# MCU.net
KiCad netlist of a schematic drawn in Altium Designer
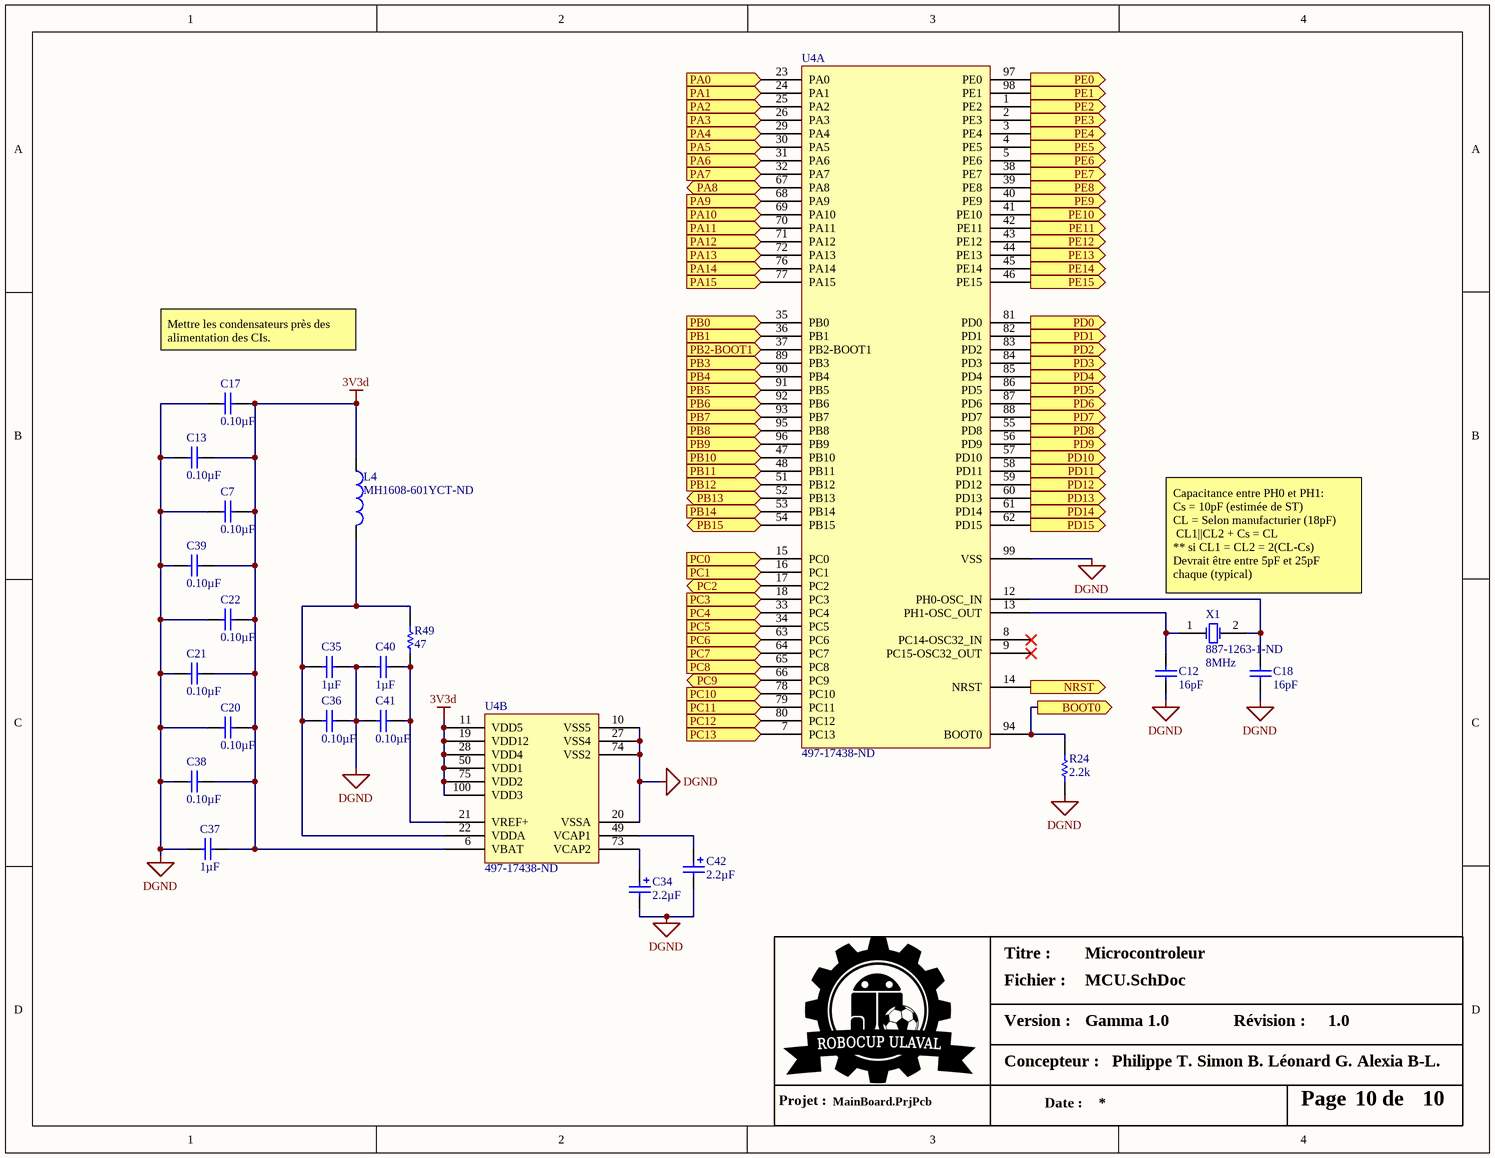
[diagram p0: MCU.SchDoc]

(export (version "E")
  (design (tool "Eeschema 10.0.6"))
  (components
    (comp (ref "C7")
      (value "CL10B104KB8SFNC")
      (footprint "0603")
      (description "CAP CER 0.1UF 50V X7R 0603")
      (fields
        (field (name "MANUFACTURER") "Samsung Electro-Mechanics America, Inc.")
        (field (name "TOLERANCE") "±10%")
        (field (name "CAPACITANCE") "0.10µF")
      )
      (libsource (lib "ResCap") (part "CL10B104KB8SFNC"))
    )
    (comp (ref "C12")
      (value "CL10C160JB8NNNC")
      (footprint "0603")
      (description "CAP CER 16PF 50V NP0 0603")
      (fields
        (field (name "MANUFACTURER") "Samsung Electro-Mechanics America, Inc.")
        (field (name "TOLERANCE") "±5%")
        (field (name "CAPACITANCE") "16pF")
      )
      (libsource (lib "ResCap") (part "CL10C160JB8NNNC"))
    )
    (comp (ref "C13")
      (value "CL10B104KB8SFNC")
      (footprint "0603")
      (description "CAP CER 0.1UF 50V X7R 0603")
      (fields
        (field (name "MANUFACTURER") "Samsung Electro-Mechanics America, Inc.")
        (field (name "TOLERANCE") "±10%")
        (field (name "CAPACITANCE") "0.10µF")
      )
      (libsource (lib "ResCap") (part "CL10B104KB8SFNC"))
    )
    (comp (ref "C17")
      (value "CL10B104KB8SFNC")
      (footprint "0603")
      (description "CAP CER 0.1UF 50V X7R 0603")
      (fields
        (field (name "MANUFACTURER") "Samsung Electro-Mechanics America, Inc.")
        (field (name "TOLERANCE") "±10%")
        (field (name "CAPACITANCE") "0.10µF")
      )
      (libsource (lib "ResCap") (part "CL10B104KB8SFNC"))
    )
    (comp (ref "C18")
      (value "CL10C160JB8NNNC")
      (footprint "0603")
      (description "CAP CER 16PF 50V NP0 0603")
      (fields
        (field (name "MANUFACTURER") "Samsung Electro-Mechanics America, Inc.")
        (field (name "TOLERANCE") "±5%")
        (field (name "CAPACITANCE") "16pF")
      )
      (libsource (lib "ResCap") (part "CL10C160JB8NNNC"))
    )
    (comp (ref "C20")
      (value "CL10B104KB8SFNC")
      (footprint "0603")
      (description "CAP CER 0.1UF 50V X7R 0603")
      (fields
        (field (name "MANUFACTURER") "Samsung Electro-Mechanics America, Inc.")
        (field (name "TOLERANCE") "±10%")
        (field (name "CAPACITANCE") "0.10µF")
      )
      (libsource (lib "ResCap") (part "CL10B104KB8SFNC"))
    )
    (comp (ref "C21")
      (value "CL10B104KB8SFNC")
      (footprint "0603")
      (description "CAP CER 0.1UF 50V X7R 0603")
      (fields
        (field (name "MANUFACTURER") "Samsung Electro-Mechanics America, Inc.")
        (field (name "TOLERANCE") "±10%")
        (field (name "CAPACITANCE") "0.10µF")
      )
      (libsource (lib "ResCap") (part "CL10B104KB8SFNC"))
    )
    (comp (ref "C22")
      (value "CL10B104KB8SFNC")
      (footprint "0603")
      (description "CAP CER 0.1UF 50V X7R 0603")
      (fields
        (field (name "MANUFACTURER") "Samsung Electro-Mechanics America, Inc.")
        (field (name "TOLERANCE") "±10%")
        (field (name "CAPACITANCE") "0.10µF")
      )
      (libsource (lib "ResCap") (part "CL10B104KB8SFNC"))
    )
    (comp (ref "C34")
      (value "865060640002")
      (footprint "CAP 4.3x4.3mm")
      (description "CAP 2.2 UF 20% 50 V")
      (fields
        (field (name "MANUFACTURER") "Wurth Electronics Inc")
        (field (name "TOLERANCE") "±20%")
        (field (name "CAPACITANCE") "2.2µF")
      )
      (libsource (lib "ResCap") (part "865060640002"))
    )
    (comp (ref "C35")
      (value "CL21B105KBFNFNE")
      (footprint "0805")
      (description "CAP CER 1UF 50V X7R 0805")
      (fields
        (field (name "MANUFACTURER") "Samsung Electro-Mechanics America, Inc.")
        (field (name "TOLERANCE") "±10%")
        (field (name "CAPACITANCE") "1µF")
      )
      (libsource (lib "ResCap") (part "CL21B105KBFNFNE"))
    )
    (comp (ref "C36")
      (value "CL10B104KB8SFNC")
      (footprint "0603")
      (description "CAP CER 0.1UF 50V X7R 0603")
      (fields
        (field (name "MANUFACTURER") "Samsung Electro-Mechanics America, Inc.")
        (field (name "TOLERANCE") "±10%")
        (field (name "CAPACITANCE") "0.10µF")
      )
      (libsource (lib "ResCap") (part "CL10B104KB8SFNC"))
    )
    (comp (ref "C37")
      (value "CL21B105KBFNFNE")
      (footprint "0805")
      (description "CAP CER 1UF 50V X7R 0805")
      (fields
        (field (name "MANUFACTURER") "Samsung Electro-Mechanics America, Inc.")
        (field (name "TOLERANCE") "±10%")
        (field (name "CAPACITANCE") "1µF")
      )
      (libsource (lib "ResCap") (part "CL21B105KBFNFNE"))
    )
    (comp (ref "C38")
      (value "CL10B104KB8SFNC")
      (footprint "0603")
      (description "CAP CER 0.1UF 50V X7R 0603")
      (fields
        (field (name "MANUFACTURER") "Samsung Electro-Mechanics America, Inc.")
        (field (name "TOLERANCE") "±10%")
        (field (name "CAPACITANCE") "0.10µF")
      )
      (libsource (lib "ResCap") (part "CL10B104KB8SFNC"))
    )
    (comp (ref "C39")
      (value "CL10B104KB8SFNC")
      (footprint "0603")
      (description "CAP CER 0.1UF 50V X7R 0603")
      (fields
        (field (name "MANUFACTURER") "Samsung Electro-Mechanics America, Inc.")
        (field (name "TOLERANCE") "±10%")
        (field (name "CAPACITANCE") "0.10µF")
      )
      (libsource (lib "ResCap") (part "CL10B104KB8SFNC"))
    )
    (comp (ref "C40")
      (value "CL21B105KBFNFNE")
      (footprint "0805")
      (description "CAP CER 1UF 50V X7R 0805")
      (fields
        (field (name "MANUFACTURER") "Samsung Electro-Mechanics America, Inc.")
        (field (name "TOLERANCE") "±10%")
        (field (name "CAPACITANCE") "1µF")
      )
      (libsource (lib "ResCap") (part "CL21B105KBFNFNE"))
    )
    (comp (ref "C41")
      (value "CL10B104KB8SFNC")
      (footprint "0603")
      (description "CAP CER 0.1UF 50V X7R 0603")
      (fields
        (field (name "MANUFACTURER") "Samsung Electro-Mechanics America, Inc.")
        (field (name "TOLERANCE") "±10%")
        (field (name "CAPACITANCE") "0.10µF")
      )
      (libsource (lib "ResCap") (part "CL10B104KB8SFNC"))
    )
    (comp (ref "C42")
      (value "865060640002")
      (footprint "CAP 4.3x4.3mm")
      (description "CAP 2.2 UF 20% 50 V")
      (fields
        (field (name "MANUFACTURER") "Wurth Electronics Inc")
        (field (name "TOLERANCE") "±20%")
        (field (name "CAPACITANCE") "2.2µF")
      )
      (libsource (lib "ResCap") (part "865060640002"))
    )
    (comp (ref "L4")
      (value "MH1608-601Y")
      (footprint "0603")
      (description "FERRITE BEAD 600 OHM 0603 1LN")
      (fields
        (field (name "MANUFACTURER") "Bourns Inc.")
        (field (name "SUPPLIER PART NUMBER 1") "MH1608-601YCT-ND")
      )
      (libsource (lib "MainBoard") (part "MH1608-601Y"))
    )
    (comp (ref "R24")
      (value "RC0603FR-072K2L")
      (footprint "0603")
      (description "RES SMD 2.2K OHM 1% 1/10W 0603")
      (fields
        (field (name "MANUFACTURER") "Yageo")
        (field (name "TOLERANCE") "±1%")
        (field (name "RESISTANCE (OHMS)") "2.2k")
      )
      (libsource (lib "ResCap") (part "RC0603FR-072K2L"))
    )
    (comp (ref "R49")
      (value "RC0603JR-0747RL")
      (footprint "0603")
      (description "RES SMD 47 OHM 5% 1/10W 0603")
      (fields
        (field (name "MANUFACTURER") "Yageo")
        (field (name "TOLERANCE") "±5%")
        (field (name "RESISTANCE (OHMS)") "47")
      )
      (libsource (lib "ResCap") (part "RC0603JR-0747RL"))
    )
    (comp (ref "U4")
      (value "STM32F407VGT6")
      (footprint "TSQFP50P1600X1600X160-100N")
      (description "IC MCU 32BIT 1MB FLASH 100LQFP")
      (fields
        (field (name "MANUFACTURER") "STMicroelectronics")
        (field (name "SUPPLIER PART NUMBER 1") "497-17438-ND")
      )
      (libsource (lib "MainBoard") (part "STM32F407VGT6"))
    )
    (comp (ref "X1")
      (value "9C-8.000MEEJ-T")
      (footprint "HC49/US")
      (description "CRYSTAL 8.0000MHZ 18PF SMD")
      (fields
        (field (name "MANUFACTURER") "TXC CORPORATION")
        (field (name "SUPPLIER PART NUMBER 1") "887-1263-1-ND")
        (field (name "FREQUENCY") "8MHz")
      )
      (libsource (lib "MainBoard") (part "9C-8.000MEEJ-T"))
    )
  )
  (nets
    (net (code "1") (name "/BOOT0") (class "Default")
      (node (ref "R24") (pin "2") (pinfunction "2_2") (pintype "passive"))
      (node (ref "U4") (pin "94") (pinfunction "BOOT0_94") (pintype "passive"))
    )
    (net (code "2") (name "/NRST") (class "Default")
      (node (ref "U4") (pin "14") (pinfunction "NRST_14") (pintype "passive"))
    )
    (net (code "3") (name "/PA0") (class "Default")
      (node (ref "U4") (pin "23") (pinfunction "PA0_23") (pintype "passive"))
    )
    (net (code "4") (name "/PA1") (class "Default")
      (node (ref "U4") (pin "24") (pinfunction "PA1_24") (pintype "passive"))
    )
    (net (code "5") (name "/PA2") (class "Default")
      (node (ref "U4") (pin "25") (pinfunction "PA2_25") (pintype "passive"))
    )
    (net (code "6") (name "/PA3") (class "Default")
      (node (ref "U4") (pin "26") (pinfunction "PA3_26") (pintype "passive"))
    )
    (net (code "7") (name "/PA4") (class "Default")
      (node (ref "U4") (pin "29") (pinfunction "PA4_29") (pintype "passive"))
    )
    (net (code "8") (name "/PA5") (class "Default")
      (node (ref "U4") (pin "30") (pinfunction "PA5_30") (pintype "passive"))
    )
    (net (code "9") (name "/PA6") (class "Default")
      (node (ref "U4") (pin "31") (pinfunction "PA6_31") (pintype "passive"))
    )
    (net (code "10") (name "/PA7") (class "Default")
      (node (ref "U4") (pin "32") (pinfunction "PA7_32") (pintype "passive"))
    )
    (net (code "11") (name "/PA8") (class "Default")
      (node (ref "U4") (pin "67") (pinfunction "PA8_67") (pintype "passive"))
    )
    (net (code "12") (name "/PA9") (class "Default")
      (node (ref "U4") (pin "68") (pinfunction "PA9_68") (pintype "passive"))
    )
    (net (code "13") (name "/PA10") (class "Default")
      (node (ref "U4") (pin "69") (pinfunction "PA10_69") (pintype "passive"))
    )
    (net (code "14") (name "/PA11") (class "Default")
      (node (ref "U4") (pin "70") (pinfunction "PA11_70") (pintype "passive"))
    )
    (net (code "15") (name "/PA12") (class "Default")
      (node (ref "U4") (pin "71") (pinfunction "PA12_71") (pintype "passive"))
    )
    (net (code "16") (name "/PA13") (class "Default")
      (node (ref "U4") (pin "72") (pinfunction "PA13_72") (pintype "passive"))
    )
    (net (code "17") (name "/PA14") (class "Default")
      (node (ref "U4") (pin "76") (pinfunction "PA14_76") (pintype "passive"))
    )
    (net (code "18") (name "/PA15") (class "Default")
      (node (ref "U4") (pin "77") (pinfunction "PA15_77") (pintype "passive"))
    )
    (net (code "19") (name "/PB0") (class "Default")
      (node (ref "U4") (pin "35") (pinfunction "PB0_35") (pintype "passive"))
    )
    (net (code "20") (name "/PB1") (class "Default")
      (node (ref "U4") (pin "36") (pinfunction "PB1_36") (pintype "passive"))
    )
    (net (code "21") (name "/PB2-BOOT1") (class "Default")
      (node (ref "U4") (pin "37") (pinfunction "PB2-BOOT1_37") (pintype "passive"))
    )
    (net (code "22") (name "/PB3") (class "Default")
      (node (ref "U4") (pin "89") (pinfunction "PB3_89") (pintype "passive"))
    )
    (net (code "23") (name "/PB4") (class "Default")
      (node (ref "U4") (pin "90") (pinfunction "PB4_90") (pintype "passive"))
    )
    (net (code "24") (name "/PB5") (class "Default")
      (node (ref "U4") (pin "91") (pinfunction "PB5_91") (pintype "passive"))
    )
    (net (code "25") (name "/PB6") (class "Default")
      (node (ref "U4") (pin "92") (pinfunction "PB6_92") (pintype "passive"))
    )
    (net (code "26") (name "/PB7") (class "Default")
      (node (ref "U4") (pin "93") (pinfunction "PB7_93") (pintype "passive"))
    )
    (net (code "27") (name "/PB8") (class "Default")
      (node (ref "U4") (pin "95") (pinfunction "PB8_95") (pintype "passive"))
    )
    (net (code "28") (name "/PB9") (class "Default")
      (node (ref "U4") (pin "96") (pinfunction "PB9_96") (pintype "passive"))
    )
    (net (code "29") (name "/PB10") (class "Default")
      (node (ref "U4") (pin "47") (pinfunction "PB10_47") (pintype "passive"))
    )
    (net (code "30") (name "/PB11") (class "Default")
      (node (ref "U4") (pin "48") (pinfunction "PB11_48") (pintype "passive"))
    )
    (net (code "31") (name "/PB12") (class "Default")
      (node (ref "U4") (pin "51") (pinfunction "PB12_51") (pintype "passive"))
    )
    (net (code "32") (name "/PB13") (class "Default")
      (node (ref "U4") (pin "52") (pinfunction "PB13_52") (pintype "passive"))
    )
    (net (code "33") (name "/PB14") (class "Default")
      (node (ref "U4") (pin "53") (pinfunction "PB14_53") (pintype "passive"))
    )
    (net (code "34") (name "/PB15") (class "Default")
      (node (ref "U4") (pin "54") (pinfunction "PB15_54") (pintype "passive"))
    )
    (net (code "35") (name "/PC0") (class "Default")
      (node (ref "U4") (pin "15") (pinfunction "PC0_15") (pintype "passive"))
    )
    (net (code "36") (name "/PC1") (class "Default")
      (node (ref "U4") (pin "16") (pinfunction "PC1_16") (pintype "passive"))
    )
    (net (code "37") (name "/PC2") (class "Default")
      (node (ref "U4") (pin "17") (pinfunction "PC2_17") (pintype "passive"))
    )
    (net (code "38") (name "/PC3") (class "Default")
      (node (ref "U4") (pin "18") (pinfunction "PC3_18") (pintype "passive"))
    )
    (net (code "39") (name "/PC4") (class "Default")
      (node (ref "U4") (pin "33") (pinfunction "PC4_33") (pintype "passive"))
    )
    (net (code "40") (name "/PC5") (class "Default")
      (node (ref "U4") (pin "34") (pinfunction "PC5_34") (pintype "passive"))
    )
    (net (code "41") (name "/PC6") (class "Default")
      (node (ref "U4") (pin "63") (pinfunction "PC6_63") (pintype "passive"))
    )
    (net (code "42") (name "/PC7") (class "Default")
      (node (ref "U4") (pin "64") (pinfunction "PC7_64") (pintype "passive"))
    )
    (net (code "43") (name "/PC8") (class "Default")
      (node (ref "U4") (pin "65") (pinfunction "PC8_65") (pintype "passive"))
    )
    (net (code "44") (name "/PC9") (class "Default")
      (node (ref "U4") (pin "66") (pinfunction "PC9_66") (pintype "passive"))
    )
    (net (code "45") (name "/PC10") (class "Default")
      (node (ref "U4") (pin "78") (pinfunction "PC10_78") (pintype "passive"))
    )
    (net (code "46") (name "/PC11") (class "Default")
      (node (ref "U4") (pin "79") (pinfunction "PC11_79") (pintype "passive"))
    )
    (net (code "47") (name "/PC12") (class "Default")
      (node (ref "U4") (pin "80") (pinfunction "PC12_80") (pintype "passive"))
    )
    (net (code "48") (name "/PC13") (class "Default")
      (node (ref "U4") (pin "7") (pinfunction "PC13_7") (pintype "passive"))
    )
    (net (code "49") (name "/PD0") (class "Default")
      (node (ref "U4") (pin "81") (pinfunction "PD0_81") (pintype "passive"))
    )
    (net (code "50") (name "/PD1") (class "Default")
      (node (ref "U4") (pin "82") (pinfunction "PD1_82") (pintype "passive"))
    )
    (net (code "51") (name "/PD2") (class "Default")
      (node (ref "U4") (pin "83") (pinfunction "PD2_83") (pintype "passive"))
    )
    (net (code "52") (name "/PD3") (class "Default")
      (node (ref "U4") (pin "84") (pinfunction "PD3_84") (pintype "passive"))
    )
    (net (code "53") (name "/PD4") (class "Default")
      (node (ref "U4") (pin "85") (pinfunction "PD4_85") (pintype "passive"))
    )
    (net (code "54") (name "/PD5") (class "Default")
      (node (ref "U4") (pin "86") (pinfunction "PD5_86") (pintype "passive"))
    )
    (net (code "55") (name "/PD6") (class "Default")
      (node (ref "U4") (pin "87") (pinfunction "PD6_87") (pintype "passive"))
    )
    (net (code "56") (name "/PD7") (class "Default")
      (node (ref "U4") (pin "88") (pinfunction "PD7_88") (pintype "passive"))
    )
    (net (code "57") (name "/PD8") (class "Default")
      (node (ref "U4") (pin "55") (pinfunction "PD8_55") (pintype "passive"))
    )
    (net (code "58") (name "/PD9") (class "Default")
      (node (ref "U4") (pin "56") (pinfunction "PD9_56") (pintype "passive"))
    )
    (net (code "59") (name "/PD10") (class "Default")
      (node (ref "U4") (pin "57") (pinfunction "PD10_57") (pintype "passive"))
    )
    (net (code "60") (name "/PD11") (class "Default")
      (node (ref "U4") (pin "58") (pinfunction "PD11_58") (pintype "passive"))
    )
    (net (code "61") (name "/PD12") (class "Default")
      (node (ref "U4") (pin "59") (pinfunction "PD12_59") (pintype "passive"))
    )
    (net (code "62") (name "/PD13") (class "Default")
      (node (ref "U4") (pin "60") (pinfunction "PD13_60") (pintype "passive"))
    )
    (net (code "63") (name "/PD14") (class "Default")
      (node (ref "U4") (pin "61") (pinfunction "PD14_61") (pintype "passive"))
    )
    (net (code "64") (name "/PD15") (class "Default")
      (node (ref "U4") (pin "62") (pinfunction "PD15_62") (pintype "passive"))
    )
    (net (code "65") (name "/PE0") (class "Default")
      (node (ref "U4") (pin "97") (pinfunction "PE0_97") (pintype "passive"))
    )
    (net (code "66") (name "/PE1") (class "Default")
      (node (ref "U4") (pin "98") (pinfunction "PE1_98") (pintype "passive"))
    )
    (net (code "67") (name "/PE2") (class "Default")
      (node (ref "U4") (pin "1") (pinfunction "PE2_1") (pintype "passive"))
    )
    (net (code "68") (name "/PE3") (class "Default")
      (node (ref "U4") (pin "2") (pinfunction "PE3_2") (pintype "passive"))
    )
    (net (code "69") (name "/PE4") (class "Default")
      (node (ref "U4") (pin "3") (pinfunction "PE4_3") (pintype "passive"))
    )
    (net (code "70") (name "/PE5") (class "Default")
      (node (ref "U4") (pin "4") (pinfunction "PE5_4") (pintype "passive"))
    )
    (net (code "71") (name "/PE6") (class "Default")
      (node (ref "U4") (pin "5") (pinfunction "PE6_5") (pintype "passive"))
    )
    (net (code "72") (name "/PE7") (class "Default")
      (node (ref "U4") (pin "38") (pinfunction "PE7_38") (pintype "passive"))
    )
    (net (code "73") (name "/PE8") (class "Default")
      (node (ref "U4") (pin "39") (pinfunction "PE8_39") (pintype "passive"))
    )
    (net (code "74") (name "/PE9") (class "Default")
      (node (ref "U4") (pin "40") (pinfunction "PE9_40") (pintype "passive"))
    )
    (net (code "75") (name "/PE10") (class "Default")
      (node (ref "U4") (pin "41") (pinfunction "PE10_41") (pintype "passive"))
    )
    (net (code "76") (name "/PE11") (class "Default")
      (node (ref "U4") (pin "42") (pinfunction "PE11_42") (pintype "passive"))
    )
    (net (code "77") (name "/PE12") (class "Default")
      (node (ref "U4") (pin "43") (pinfunction "PE12_43") (pintype "passive"))
    )
    (net (code "78") (name "/PE13") (class "Default")
      (node (ref "U4") (pin "44") (pinfunction "PE13_44") (pintype "passive"))
    )
    (net (code "79") (name "/PE14") (class "Default")
      (node (ref "U4") (pin "45") (pinfunction "PE14_45") (pintype "passive"))
    )
    (net (code "80") (name "/PE15") (class "Default")
      (node (ref "U4") (pin "46") (pinfunction "PE15_46") (pintype "passive"))
    )
    (net (code "81") (name "3V3d") (class "Default")
      (node (ref "C13") (pin "2") (pinfunction "2_2") (pintype "passive"))
      (node (ref "C17") (pin "2") (pinfunction "2_2") (pintype "passive"))
      (node (ref "C20") (pin "2") (pinfunction "2_2") (pintype "passive"))
      (node (ref "C21") (pin "2") (pinfunction "2_2") (pintype "passive"))
      (node (ref "C22") (pin "2") (pinfunction "2_2") (pintype "passive"))
      (node (ref "C37") (pin "2") (pinfunction "2_2") (pintype "passive"))
      (node (ref "C38") (pin "2") (pinfunction "2_2") (pintype "passive"))
      (node (ref "C39") (pin "2") (pinfunction "2_2") (pintype "passive"))
      (node (ref "C7") (pin "2") (pinfunction "2_2") (pintype "passive"))
      (node (ref "L4") (pin "1") (pinfunction "1_1") (pintype "passive"))
      (node (ref "U4") (pin "100") (pinfunction "VDD3_100") (pintype "power_in"))
      (node (ref "U4") (pin "11") (pinfunction "VDD5_11") (pintype "power_in"))
      (node (ref "U4") (pin "19") (pinfunction "VDD12_19") (pintype "power_in"))
      (node (ref "U4") (pin "28") (pinfunction "VDD4_28") (pintype "power_in"))
      (node (ref "U4") (pin "50") (pinfunction "VDD1_50") (pintype "power_in"))
      (node (ref "U4") (pin "6") (pinfunction "VBAT_6") (pintype "power_in"))
      (node (ref "U4") (pin "75") (pinfunction "VDD2_75") (pintype "power_in"))
    )
    (net (code "82") (name "DGND") (class "Default")
      (node (ref "C12") (pin "1") (pinfunction "1_1") (pintype "passive"))
      (node (ref "C13") (pin "1") (pinfunction "1_1") (pintype "passive"))
      (node (ref "C17") (pin "1") (pinfunction "1_1") (pintype "passive"))
      (node (ref "C18") (pin "1") (pinfunction "1_1") (pintype "passive"))
      (node (ref "C20") (pin "1") (pinfunction "1_1") (pintype "passive"))
      (node (ref "C21") (pin "1") (pinfunction "1_1") (pintype "passive"))
      (node (ref "C22") (pin "1") (pinfunction "1_1") (pintype "passive"))
      (node (ref "C34") (pin "2") (pinfunction "2_2") (pintype "passive"))
      (node (ref "C35") (pin "2") (pinfunction "2_2") (pintype "passive"))
      (node (ref "C36") (pin "2") (pinfunction "2_2") (pintype "passive"))
      (node (ref "C37") (pin "1") (pinfunction "1_1") (pintype "passive"))
      (node (ref "C38") (pin "1") (pinfunction "1_1") (pintype "passive"))
      (node (ref "C39") (pin "1") (pinfunction "1_1") (pintype "passive"))
      (node (ref "C40") (pin "1") (pinfunction "1_1") (pintype "passive"))
      (node (ref "C41") (pin "1") (pinfunction "1_1") (pintype "passive"))
      (node (ref "C42") (pin "2") (pinfunction "2_2") (pintype "passive"))
      (node (ref "C7") (pin "1") (pinfunction "1_1") (pintype "passive"))
      (node (ref "R24") (pin "1") (pinfunction "1_1") (pintype "passive"))
      (node (ref "U4") (pin "10") (pinfunction "VSS5_10") (pintype "power_in"))
      (node (ref "U4") (pin "20") (pinfunction "VSSA_20") (pintype "power_in"))
      (node (ref "U4") (pin "27") (pinfunction "VSS4_27") (pintype "power_in"))
      (node (ref "U4") (pin "74") (pinfunction "VSS2_74") (pintype "power_in"))
      (node (ref "U4") (pin "99") (pinfunction "VSS_99") (pintype "power_in"))
    )
    (net (code "83") (name "Net-(U4A-PH0-OSC_IN)") (class "Default")
      (node (ref "C18") (pin "2") (pinfunction "2_2") (pintype "passive"))
      (node (ref "U4") (pin "12") (pinfunction "PH0-OSC_IN_12") (pintype "passive"))
      (node (ref "X1") (pin "2") (pinfunction "OSC2_2") (pintype "passive"))
    )
    (net (code "84") (name "Net-(U4A-PH1-OSC_OUT)") (class "Default")
      (node (ref "C12") (pin "2") (pinfunction "2_2") (pintype "passive"))
      (node (ref "U4") (pin "13") (pinfunction "PH1-OSC_OUT_13") (pintype "passive"))
      (node (ref "X1") (pin "1") (pinfunction "OSC1_1") (pintype "passive"))
    )
    (net (code "85") (name "Net-(U4B-VCAP1)") (class "Default")
      (node (ref "C42") (pin "1") (pinfunction "1_1") (pintype "passive"))
      (node (ref "U4") (pin "49") (pinfunction "VCAP1_49") (pintype "power_in"))
    )
    (net (code "86") (name "Net-(U4B-VCAP2)") (class "Default")
      (node (ref "C34") (pin "1") (pinfunction "1_1") (pintype "passive"))
      (node (ref "U4") (pin "73") (pinfunction "VCAP2_73") (pintype "power_in"))
    )
    (net (code "87") (name "Net-(U4B-VDDA)") (class "Default")
      (node (ref "C35") (pin "1") (pinfunction "1_1") (pintype "passive"))
      (node (ref "C36") (pin "1") (pinfunction "1_1") (pintype "passive"))
      (node (ref "L4") (pin "2") (pinfunction "2_2") (pintype "passive"))
      (node (ref "R49") (pin "2") (pinfunction "2_2") (pintype "passive"))
      (node (ref "U4") (pin "22") (pinfunction "VDDA_22") (pintype "power_in"))
    )
    (net (code "88") (name "Net-(U4B-VREF+)") (class "Default")
      (node (ref "C40") (pin "2") (pinfunction "2_2") (pintype "passive"))
      (node (ref "C41") (pin "2") (pinfunction "2_2") (pintype "passive"))
      (node (ref "R49") (pin "1") (pinfunction "1_1") (pintype "passive"))
      (node (ref "U4") (pin "21") (pinfunction "VREF+_21") (pintype "power_in"))
    )
    (net (code "89") (name "unconnected-(U4A-PC14-OSC32_IN-Pad8)") (class "Default")
      (node (ref "U4") (pin "8") (pinfunction "PC14-OSC32_IN_8") (pintype "passive+no_connect"))
    )
    (net (code "90") (name "unconnected-(U4A-PC15-OSC32_OUT-Pad9)") (class "Default")
      (node (ref "U4") (pin "9") (pinfunction "PC15-OSC32_OUT_9") (pintype "passive+no_connect"))
    )
  )
)
